# Sheet1.net
KiCad netlist of a schematic drawn in Altium Designer
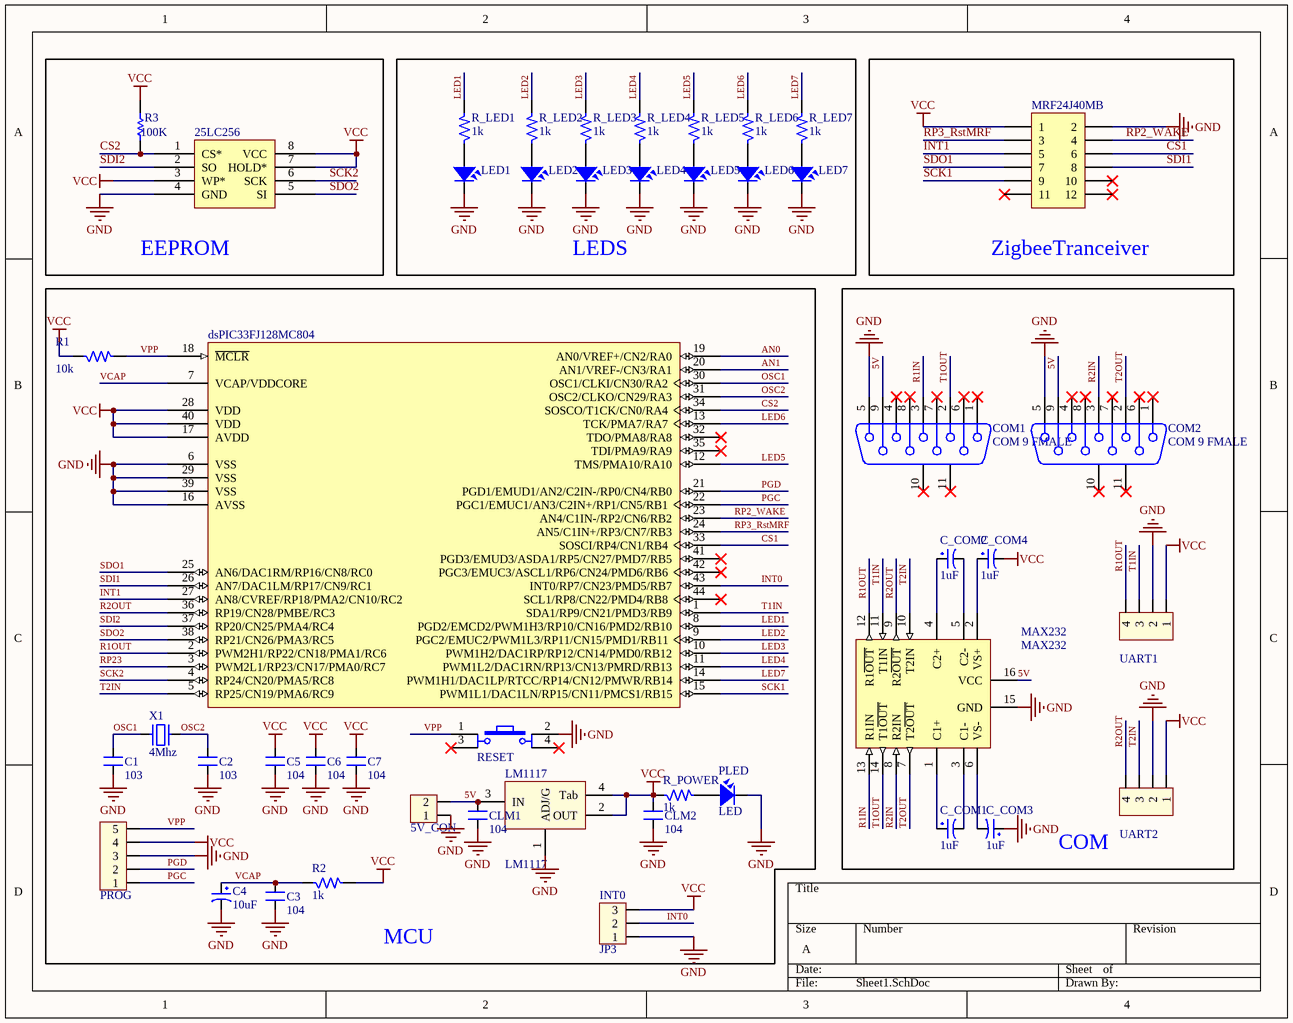
[diagram p0: Sheet1.SchDoc]

(export (version "E")
  (design (tool "Eeschema 10.0.6"))
  (components
    (comp (ref "5V_CON")
      (value "JP2")
      (footprint "CON2")
      (description "Connector 2")
      (libsource (lib "syhaunguyen") (part "Con2"))
    )
    (comp (ref "25LC256") (value "25LC256") (footprint "DIP-8") (libsource (lib "25LC256") (part "25LC256")))
    (comp (ref "C1")
      (value "103")
      (footprint "SM-0805")
      (description "Cap SMD")
      (libsource (lib "syhaunguyen") (part "CM"))
    )
    (comp (ref "C2")
      (value "103")
      (footprint "SM-0805")
      (description "Cap SMD")
      (libsource (lib "syhaunguyen") (part "CM"))
    )
    (comp (ref "C3")
      (value "104")
      (footprint "SM-0805")
      (description "Cap SMD")
      (libsource (lib "syhaunguyen") (part "CM"))
    )
    (comp (ref "C4")
      (value "10uF")
      (footprint "CP1/2")
      (description "Cap P  0,1uF < 22uF , 16 - 50V")
      (libsource (lib "") (part "CP1_1"))
    )
    (comp (ref "C5")
      (value "104")
      (footprint "SM-0805")
      (description "Cap SMD")
      (libsource (lib "syhaunguyen") (part "CM"))
    )
    (comp (ref "C6")
      (value "104")
      (footprint "SM-0805")
      (description "Cap SMD")
      (libsource (lib "syhaunguyen") (part "CM"))
    )
    (comp (ref "C7")
      (value "104")
      (footprint "SM-0805")
      (description "Cap SMD")
      (libsource (lib "syhaunguyen") (part "CM"))
    )
    (comp (ref "CLM1")
      (value "104")
      (footprint "SM-0805")
      (description "Cap np Cremic Value  104pF => 105pF")
      (libsource (lib "syhaunguyen") (part "CN2"))
    )
    (comp (ref "CLM2")
      (value "104")
      (footprint "SM-0805")
      (description "Cap np Cremic Value  104pF => 105pF")
      (libsource (lib "syhaunguyen") (part "CN2"))
    )
    (comp (ref "COM1")
      (value "COM 9 FMALE")
      (footprint "DSB 9-F")
      (description "COM 9")
      (fields (field (name "PUBLISHER") "Altium Limited"))
      (libsource (lib "syhaunguyen") (part "DSB9F"))
    )
    (comp (ref "COM2")
      (value "COM 9 FMALE")
      (footprint "DSB 9-F")
      (description "COM 9")
      (fields (field (name "PUBLISHER") "Altium Limited"))
      (libsource (lib "syhaunguyen") (part "DSB9F"))
    )
    (comp (ref "C_COM1")
      (value "1uF")
      (footprint "CP1/2")
      (description "Cap P  0,1uF < 22uF , 16 - 50V")
      (libsource (lib "syhaunguyen") (part "CP1"))
    )
    (comp (ref "C_COM2")
      (value "1uF")
      (footprint "CP1/2")
      (description "Cap P  0,1uF < 22uF , 16 - 50V")
      (libsource (lib "syhaunguyen") (part "CP1"))
    )
    (comp (ref "C_COM3")
      (value "1uF")
      (footprint "CP1/2")
      (description "Cap P  0,1uF < 22uF , 16 - 50V")
      (libsource (lib "syhaunguyen") (part "CP1"))
    )
    (comp (ref "C_COM4")
      (value "1uF")
      (footprint "CP1/2")
      (description "Cap P  0,1uF < 22uF , 16 - 50V")
      (libsource (lib "syhaunguyen") (part "CP1"))
    )
    (comp (ref "dsPIC33FJ128MC804")
      (value "DSPIC33FJ128MC804T-E/PT")
      (footprint "TQFP-PT44_N")
      (fields (field (name "PUBLISHER") "Altium Limited"))
      (libsource (lib "Microchip DSC 16-Bit dsPIC33F") (part "DSPIC33FJ128MC804T-E/PT"))
    )
    (comp (ref "INT0")
      (value "JP3")
      (footprint "CON3")
      (description "Connector 3")
      (libsource (lib "syhaunguyen") (part "Con3"))
    )
    (comp (ref "LED1")
      (value "LED")
      (footprint "SM-LED-Red")
      (description "Led  Vuong")
      (libsource (lib "syhaunguyen") (part "LED"))
    )
    (comp (ref "LED2")
      (value "LED")
      (footprint "SM-LED-Red")
      (description "Led  Vuong")
      (libsource (lib "syhaunguyen") (part "LED"))
    )
    (comp (ref "LED3")
      (value "LED")
      (footprint "SM-LED-Red")
      (description "Led  Vuong")
      (libsource (lib "syhaunguyen") (part "LED"))
    )
    (comp (ref "LED4")
      (value "LED")
      (footprint "SM-LED-Red")
      (description "Led  Vuong")
      (libsource (lib "syhaunguyen") (part "LED"))
    )
    (comp (ref "LED5")
      (value "LED")
      (footprint "SM-LED-Red")
      (description "Led  Vuong")
      (libsource (lib "syhaunguyen") (part "LED"))
    )
    (comp (ref "LED6")
      (value "LED")
      (footprint "SM-LED-Red")
      (description "Led  Vuong")
      (libsource (lib "syhaunguyen") (part "LED"))
    )
    (comp (ref "LED7")
      (value "LED")
      (footprint "SM-LED-Red")
      (description "Led  Vuong")
      (libsource (lib "syhaunguyen") (part "LED"))
    )
    (comp (ref "LM1117")
      (value "LM1117")
      (footprint "SOT223-4N")
      (description "3v3")
      (libsource (lib "syhaunguyen") (part "LM1117"))
    )
    (comp (ref "MAX232")
      (value "MAX232")
      (footprint "SOP16")
      (description "Dual EIA-232 Driver/Receiver")
      (libsource (lib "syhaunguyen") (part "MAX232"))
    )
    (comp (ref "MRF24J40MB")
      (value "Header 6X2")
      (footprint "MRF24J40MB_board_mini")
      (description "Header, 6-Pin, Dual row")
      (fields (field (name "PUBLISHER") "Altium Limited"))
      (libsource (lib "Miscellaneous Connectors") (part "Header 6X2"))
    )
    (comp (ref "PLED")
      (value "LED")
      (footprint "LED-3")
      (description "Led  Vuong")
      (libsource (lib "syhaunguyen") (part "LED"))
    )
    (comp (ref "PROG")
      (value "JP5")
      (footprint "CON5")
      (description "Connector 5")
      (libsource (lib "syhaunguyen") (part "Con5"))
    )
    (comp (ref "R1")
      (value "10k")
      (footprint "C0805")
      (description "Resistor 1/4W")
      (libsource (lib "syhaunguyen") (part "R"))
    )
    (comp (ref "R2")
      (value "1k")
      (footprint "SM-0805")
      (description "Resistor 1/4W")
      (libsource (lib "syhaunguyen") (part "R"))
    )
    (comp (ref "R3")
      (value "100K")
      (footprint "C0805")
      (description "Semiconductor Resistor")
      (fields (field (name "Comment") "Res Semi") (field (name "PUBLISHER") "Altium Limited"))
      (libsource (lib "Miscellaneous Devices") (part "Res Semi"))
    )
    (comp (ref "RESET")
      (value "SW")
      (footprint "SW4")
      (description "Switch button 4 pin")
      (libsource (lib "syhaunguyen") (part "SW4"))
    )
    (comp (ref "R_LED1")
      (value "1k")
      (footprint "SM-0805")
      (description "Resistor 1/4W")
      (libsource (lib "syhaunguyen") (part "R"))
    )
    (comp (ref "R_LED2")
      (value "1k")
      (footprint "SM-0805")
      (description "Resistor 1/4W")
      (libsource (lib "syhaunguyen") (part "R"))
    )
    (comp (ref "R_LED3")
      (value "1k")
      (footprint "SM-0805")
      (description "Resistor 1/4W")
      (libsource (lib "syhaunguyen") (part "R"))
    )
    (comp (ref "R_LED4")
      (value "1k")
      (footprint "SM-0805")
      (description "Resistor 1/4W")
      (libsource (lib "syhaunguyen") (part "R"))
    )
    (comp (ref "R_LED5")
      (value "1k")
      (footprint "SM-0805")
      (description "Resistor 1/4W")
      (libsource (lib "syhaunguyen") (part "R"))
    )
    (comp (ref "R_LED6")
      (value "1k")
      (footprint "SM-0805")
      (description "Resistor 1/4W")
      (libsource (lib "syhaunguyen") (part "R"))
    )
    (comp (ref "R_LED7")
      (value "1k")
      (footprint "SM-0805")
      (description "Resistor 1/4W")
      (libsource (lib "syhaunguyen") (part "R"))
    )
    (comp (ref "R_POWER")
      (value "1k")
      (footprint "SM-0805")
      (description "Resistor 1/4W")
      (libsource (lib "syhaunguyen") (part "R"))
    )
    (comp (ref "UART1")
      (value "JP4")
      (footprint "CON4")
      (description "Connector 4")
      (libsource (lib "syhaunguyen") (part "Con4"))
    )
    (comp (ref "UART2")
      (value "JP4")
      (footprint "CON4")
      (description "Connector 4")
      (libsource (lib "syhaunguyen") (part "Con4"))
    )
    (comp (ref "X1")
      (value "4Mhz")
      (footprint "XT2")
      (description "Crystal For all Crystal 2pin.")
      (libsource (lib "syhaunguyen") (part "XT2"))
    )
  )
  (nets
    (net (code "1") (name "/5V") (class "Default")
      (node (ref "5V_CON") (pin "2") (pinfunction "2_2") (pintype "passive"))
      (node (ref "CLM1") (pin "2") (pinfunction "2_2") (pintype "passive"))
      (node (ref "COM1") (pin "9") (pinfunction "9_9") (pintype "passive"))
      (node (ref "COM2") (pin "9") (pinfunction "9_9") (pintype "passive"))
      (node (ref "LM1117") (pin "3") (pinfunction "IN_3") (pintype "passive"))
      (node (ref "MAX232") (pin "16") (pinfunction "VCC_16") (pintype "power_in"))
    )
    (net (code "2") (name "/AN0") (class "Default")
      (node (ref "dsPIC33FJ128MC804") (pin "19") (pinfunction "AN0/VREF+/CN2/RA0_19") (pintype "bidirectional"))
    )
    (net (code "3") (name "/AN1") (class "Default")
      (node (ref "dsPIC33FJ128MC804") (pin "20") (pinfunction "AN1/VREF-/CN3/RA1_20") (pintype "bidirectional"))
    )
    (net (code "4") (name "/CS1") (class "Default")
      (node (ref "MRF24J40MB") (pin "6") (pinfunction "6_6") (pintype "passive"))
      (node (ref "dsPIC33FJ128MC804") (pin "33") (pinfunction "SOSCI/RP4/CN1/RB4_33") (pintype "bidirectional"))
    )
    (net (code "5") (name "/CS2") (class "Default")
      (node (ref "25LC256") (pin "1") (pinfunction "CS*_1") (pintype "passive"))
      (node (ref "R3") (pin "1") (pinfunction "1_1") (pintype "passive"))
      (node (ref "dsPIC33FJ128MC804") (pin "34") (pinfunction "SOSCO/T1CK/CN0/RA4_34") (pintype "bidirectional"))
    )
    (net (code "6") (name "/INT0") (class "Default")
      (node (ref "INT0") (pin "2") (pinfunction "2_2") (pintype "passive"))
      (node (ref "dsPIC33FJ128MC804") (pin "43") (pinfunction "INT0/RP7/CN23/PMD5/RB7_43") (pintype "bidirectional"))
    )
    (net (code "7") (name "/INT1") (class "Default")
      (node (ref "MRF24J40MB") (pin "5") (pinfunction "5_5") (pintype "passive"))
      (node (ref "dsPIC33FJ128MC804") (pin "27") (pinfunction "AN8/CVREF/RP18/PMA2/CN10/RC2_27") (pintype "bidirectional"))
    )
    (net (code "8") (name "/LED1") (class "Default")
      (node (ref "R_LED1") (pin "2") (pinfunction "2_2") (pintype "passive"))
      (node (ref "dsPIC33FJ128MC804") (pin "8") (pinfunction "PGD2/EMCD2/PWM1H3/RP10/CN16/PMD2/RB10_8") (pintype "bidirectional"))
    )
    (net (code "9") (name "/LED2") (class "Default")
      (node (ref "R_LED2") (pin "2") (pinfunction "2_2") (pintype "passive"))
      (node (ref "dsPIC33FJ128MC804") (pin "9") (pinfunction "PGC2/EMUC2/PWM1L3/RP11/CN15/PMD1/RB11_9") (pintype "bidirectional"))
    )
    (net (code "10") (name "/LED3") (class "Default")
      (node (ref "R_LED3") (pin "2") (pinfunction "2_2") (pintype "passive"))
      (node (ref "dsPIC33FJ128MC804") (pin "10") (pinfunction "PWM1H2/DAC1RP/RP12/CN14/PMD0/RB12_10") (pintype "bidirectional"))
    )
    (net (code "11") (name "/LED4") (class "Default")
      (node (ref "R_LED4") (pin "2") (pinfunction "2_2") (pintype "passive"))
      (node (ref "dsPIC33FJ128MC804") (pin "11") (pinfunction "PWM1L2/DAC1RN/RP13/CN13/PMRD/RB13_11") (pintype "bidirectional"))
    )
    (net (code "12") (name "/LED5") (class "Default")
      (node (ref "R_LED5") (pin "2") (pinfunction "2_2") (pintype "passive"))
      (node (ref "dsPIC33FJ128MC804") (pin "12") (pinfunction "TMS/PMA10/RA10_12") (pintype "bidirectional"))
    )
    (net (code "13") (name "/LED6") (class "Default")
      (node (ref "R_LED6") (pin "2") (pinfunction "2_2") (pintype "passive"))
      (node (ref "dsPIC33FJ128MC804") (pin "13") (pinfunction "TCK/PMA7/RA7_13") (pintype "bidirectional"))
    )
    (net (code "14") (name "/LED7") (class "Default")
      (node (ref "R_LED7") (pin "2") (pinfunction "2_2") (pintype "passive"))
      (node (ref "dsPIC33FJ128MC804") (pin "14") (pinfunction "PWM1H1/DAC1LP/RTCC/RP14/CN12/PMWR/RB14_14") (pintype "bidirectional"))
    )
    (net (code "15") (name "/OSC1") (class "Default")
      (node (ref "C1") (pin "2") (pinfunction "2_2") (pintype "passive"))
      (node (ref "X1") (pin "1") (pinfunction "1_1") (pintype "passive"))
      (node (ref "dsPIC33FJ128MC804") (pin "30") (pinfunction "OSC1/CLKI/CN30/RA2_30") (pintype "bidirectional"))
    )
    (net (code "16") (name "/OSC2") (class "Default")
      (node (ref "C2") (pin "2") (pinfunction "2_2") (pintype "passive"))
      (node (ref "X1") (pin "2") (pinfunction "2_2") (pintype "passive"))
      (node (ref "dsPIC33FJ128MC804") (pin "31") (pinfunction "OSC2/CLKO/CN29/RA3_31") (pintype "bidirectional"))
    )
    (net (code "17") (name "/PGC") (class "Default")
      (node (ref "PROG") (pin "1") (pinfunction "1_1") (pintype "passive"))
      (node (ref "dsPIC33FJ128MC804") (pin "22") (pinfunction "PGC1/EMUC1/AN3/C2IN+/RP1/CN5/RB1_22") (pintype "bidirectional"))
    )
    (net (code "18") (name "/PGD") (class "Default")
      (node (ref "PROG") (pin "2") (pinfunction "2_2") (pintype "passive"))
      (node (ref "dsPIC33FJ128MC804") (pin "21") (pinfunction "PGD1/EMUD1/AN2/C2IN-/RP0/CN4/RB0_21") (pintype "bidirectional"))
    )
    (net (code "19") (name "/R1IN") (class "Default")
      (node (ref "COM1") (pin "3") (pinfunction "3_3") (pintype "passive"))
      (node (ref "MAX232") (pin "13") (pinfunction "R1IN_13") (pintype "input"))
    )
    (net (code "20") (name "/R1OUT") (class "Default")
      (node (ref "MAX232") (pin "12") (pinfunction "R1~{OUT}_12") (pintype "output"))
      (node (ref "UART1") (pin "4") (pinfunction "4_4") (pintype "passive"))
      (node (ref "dsPIC33FJ128MC804") (pin "2") (pinfunction "PWM2H1/RP22/CN18/PMA1/RC6_2") (pintype "bidirectional"))
    )
    (net (code "21") (name "/R2IN") (class "Default")
      (node (ref "COM2") (pin "3") (pinfunction "3_3") (pintype "passive"))
      (node (ref "MAX232") (pin "8") (pinfunction "R2IN_8") (pintype "input"))
    )
    (net (code "22") (name "/R2OUT") (class "Default")
      (node (ref "MAX232") (pin "9") (pinfunction "R2~{OUT}_9") (pintype "output"))
      (node (ref "UART2") (pin "4") (pinfunction "4_4") (pintype "passive"))
      (node (ref "dsPIC33FJ128MC804") (pin "36") (pinfunction "RP19/CN28/PMBE/RC3_36") (pintype "bidirectional"))
    )
    (net (code "23") (name "/RP2_WAKE") (class "Default")
      (node (ref "MRF24J40MB") (pin "4") (pinfunction "4_4") (pintype "passive"))
      (node (ref "dsPIC33FJ128MC804") (pin "23") (pinfunction "AN4/C1IN-/RP2/CN6/RB2_23") (pintype "bidirectional"))
    )
    (net (code "24") (name "/RP3_RstMRF") (class "Default")
      (node (ref "MRF24J40MB") (pin "3") (pinfunction "3_3") (pintype "passive"))
      (node (ref "dsPIC33FJ128MC804") (pin "24") (pinfunction "AN5/C1IN+/RP3/CN7/RB3_24") (pintype "bidirectional"))
    )
    (net (code "25") (name "/RP23") (class "Default")
      (node (ref "dsPIC33FJ128MC804") (pin "3") (pinfunction "PWM2L1/RP23/CN17/PMA0/RC7_3") (pintype "bidirectional"))
    )
    (net (code "26") (name "/SCK1") (class "Default")
      (node (ref "MRF24J40MB") (pin "9") (pinfunction "9_9") (pintype "passive"))
      (node (ref "dsPIC33FJ128MC804") (pin "15") (pinfunction "PWM1L1/DAC1LN/RP15/CN11/PMCS1/RB15_15") (pintype "bidirectional"))
    )
    (net (code "27") (name "/SCK2") (class "Default")
      (node (ref "25LC256") (pin "6") (pinfunction "SCK_6") (pintype "passive"))
      (node (ref "dsPIC33FJ128MC804") (pin "4") (pinfunction "RP24/CN20/PMA5/RC8_4") (pintype "bidirectional"))
    )
    (net (code "28") (name "/SDI1") (class "Default")
      (node (ref "MRF24J40MB") (pin "8") (pinfunction "8_8") (pintype "passive"))
      (node (ref "dsPIC33FJ128MC804") (pin "26") (pinfunction "AN7/DAC1LM/RP17/CN9/RC1_26") (pintype "bidirectional"))
    )
    (net (code "29") (name "/SDI2") (class "Default")
      (node (ref "25LC256") (pin "2") (pinfunction "SO_2") (pintype "passive"))
      (node (ref "dsPIC33FJ128MC804") (pin "37") (pinfunction "RP20/CN25/PMA4/RC4_37") (pintype "bidirectional"))
    )
    (net (code "30") (name "/SDO1") (class "Default")
      (node (ref "MRF24J40MB") (pin "7") (pinfunction "7_7") (pintype "passive"))
      (node (ref "dsPIC33FJ128MC804") (pin "25") (pinfunction "AN6/DAC1RM/RP16/CN8/RC0_25") (pintype "bidirectional"))
    )
    (net (code "31") (name "/SDO2") (class "Default")
      (node (ref "25LC256") (pin "5") (pinfunction "SI_5") (pintype "passive"))
      (node (ref "dsPIC33FJ128MC804") (pin "38") (pinfunction "RP21/CN26/PMA3/RC5_38") (pintype "bidirectional"))
    )
    (net (code "32") (name "/T1IN") (class "Default")
      (node (ref "MAX232") (pin "11") (pinfunction "T1IN_11") (pintype "input"))
      (node (ref "UART1") (pin "3") (pinfunction "3_3") (pintype "passive"))
      (node (ref "dsPIC33FJ128MC804") (pin "1") (pinfunction "SDA1/RP9/CN21/PMD3/RB9_1") (pintype "bidirectional"))
    )
    (net (code "33") (name "/T1OUT") (class "Default")
      (node (ref "COM1") (pin "2") (pinfunction "2_2") (pintype "passive"))
      (node (ref "MAX232") (pin "14") (pinfunction "T1~{OUT}_14") (pintype "output"))
    )
    (net (code "34") (name "/T2IN") (class "Default")
      (node (ref "MAX232") (pin "10") (pinfunction "T2IN_10") (pintype "input"))
      (node (ref "UART2") (pin "3") (pinfunction "3_3") (pintype "passive"))
      (node (ref "dsPIC33FJ128MC804") (pin "5") (pinfunction "RP25/CN19/PMA6/RC9_5") (pintype "bidirectional"))
    )
    (net (code "35") (name "/T2OUT") (class "Default")
      (node (ref "COM2") (pin "2") (pinfunction "2_2") (pintype "passive"))
      (node (ref "MAX232") (pin "7") (pinfunction "T2~{OUT}_7") (pintype "output"))
    )
    (net (code "36") (name "/VCAP") (class "Default")
      (node (ref "C3") (pin "2") (pinfunction "2_2") (pintype "passive"))
      (node (ref "C4") (pin "1") (pinfunction "1_1") (pintype "passive"))
      (node (ref "R2") (pin "1") (pinfunction "1_1") (pintype "passive"))
      (node (ref "dsPIC33FJ128MC804") (pin "7") (pinfunction "VCAP/VDDCORE_7") (pintype "power_in"))
    )
    (net (code "37") (name "/VPP") (class "Default")
      (node (ref "PROG") (pin "5") (pinfunction "5_5") (pintype "passive"))
      (node (ref "R1") (pin "2") (pinfunction "2_2") (pintype "passive"))
      (node (ref "RESET") (pin "1") (pintype "passive"))
      (node (ref "dsPIC33FJ128MC804") (pin "18") (pinfunction "~{MCLR}_18") (pintype "input"))
    )
    (net (code "38") (name "GND") (class "Default")
      (node (ref "25LC256") (pin "4") (pinfunction "GND_4") (pintype "power_in"))
      (node (ref "5V_CON") (pin "1") (pinfunction "1_1") (pintype "passive"))
      (node (ref "C1") (pin "1") (pinfunction "1_1") (pintype "passive"))
      (node (ref "C2") (pin "1") (pinfunction "1_1") (pintype "passive"))
      (node (ref "C3") (pin "1") (pinfunction "1_1") (pintype "passive"))
      (node (ref "C4") (pin "2") (pinfunction "2_2") (pintype "passive"))
      (node (ref "C5") (pin "1") (pinfunction "1_1") (pintype "passive"))
      (node (ref "C6") (pin "1") (pinfunction "1_1") (pintype "passive"))
      (node (ref "C7") (pin "1") (pinfunction "1_1") (pintype "passive"))
      (node (ref "CLM1") (pin "1") (pinfunction "1_1") (pintype "passive"))
      (node (ref "CLM2") (pin "1") (pinfunction "1_1") (pintype "passive"))
      (node (ref "COM1") (pin "5") (pinfunction "5_5") (pintype "passive"))
      (node (ref "COM2") (pin "5") (pinfunction "5_5") (pintype "passive"))
      (node (ref "C_COM3") (pin "1") (pinfunction "1_1") (pintype "passive"))
      (node (ref "INT0") (pin "1") (pinfunction "1_1") (pintype "passive"))
      (node (ref "LED1") (pin "2") (pinfunction "2_2") (pintype "passive"))
      (node (ref "LED2") (pin "2") (pinfunction "2_2") (pintype "passive"))
      (node (ref "LED3") (pin "2") (pinfunction "2_2") (pintype "passive"))
      (node (ref "LED4") (pin "2") (pinfunction "2_2") (pintype "passive"))
      (node (ref "LED5") (pin "2") (pinfunction "2_2") (pintype "passive"))
      (node (ref "LED6") (pin "2") (pinfunction "2_2") (pintype "passive"))
      (node (ref "LED7") (pin "2") (pinfunction "2_2") (pintype "passive"))
      (node (ref "LM1117") (pin "1") (pinfunction "ADJ/G_1") (pintype "passive"))
      (node (ref "MAX232") (pin "15") (pinfunction "GND_15") (pintype "power_in"))
      (node (ref "MRF24J40MB") (pin "2") (pinfunction "2_2") (pintype "passive"))
      (node (ref "PLED") (pin "2") (pinfunction "2_2") (pintype "passive"))
      (node (ref "PROG") (pin "3") (pinfunction "3_3") (pintype "passive"))
      (node (ref "RESET") (pin "2") (pintype "passive"))
      (node (ref "UART1") (pin "2") (pinfunction "2_2") (pintype "passive"))
      (node (ref "UART2") (pin "2") (pinfunction "2_2") (pintype "passive"))
      (node (ref "dsPIC33FJ128MC804") (pin "16") (pinfunction "AVSS_16") (pintype "power_in"))
      (node (ref "dsPIC33FJ128MC804") (pin "29") (pinfunction "VSS_29") (pintype "power_in"))
      (node (ref "dsPIC33FJ128MC804") (pin "39") (pinfunction "VSS_39") (pintype "power_in"))
      (node (ref "dsPIC33FJ128MC804") (pin "6") (pinfunction "VSS_6") (pintype "power_in"))
    )
    (net (code "39") (name "Net-(LED1-Pad1)") (class "Default")
      (node (ref "LED1") (pin "1") (pinfunction "1_1") (pintype "passive"))
      (node (ref "R_LED1") (pin "1") (pinfunction "1_1") (pintype "passive"))
    )
    (net (code "40") (name "Net-(LED2-Pad1)") (class "Default")
      (node (ref "LED2") (pin "1") (pinfunction "1_1") (pintype "passive"))
      (node (ref "R_LED2") (pin "1") (pinfunction "1_1") (pintype "passive"))
    )
    (net (code "41") (name "Net-(LED3-Pad1)") (class "Default")
      (node (ref "LED3") (pin "1") (pinfunction "1_1") (pintype "passive"))
      (node (ref "R_LED3") (pin "1") (pinfunction "1_1") (pintype "passive"))
    )
    (net (code "42") (name "Net-(LED4-Pad1)") (class "Default")
      (node (ref "LED4") (pin "1") (pinfunction "1_1") (pintype "passive"))
      (node (ref "R_LED4") (pin "1") (pinfunction "1_1") (pintype "passive"))
    )
    (net (code "43") (name "Net-(LED5-Pad1)") (class "Default")
      (node (ref "LED5") (pin "1") (pinfunction "1_1") (pintype "passive"))
      (node (ref "R_LED5") (pin "1") (pinfunction "1_1") (pintype "passive"))
    )
    (net (code "44") (name "Net-(LED6-Pad1)") (class "Default")
      (node (ref "LED6") (pin "1") (pinfunction "1_1") (pintype "passive"))
      (node (ref "R_LED6") (pin "1") (pinfunction "1_1") (pintype "passive"))
    )
    (net (code "45") (name "Net-(LED7-Pad1)") (class "Default")
      (node (ref "LED7") (pin "1") (pinfunction "1_1") (pintype "passive"))
      (node (ref "R_LED7") (pin "1") (pinfunction "1_1") (pintype "passive"))
    )
    (net (code "46") (name "Net-(MAX232-C1+)") (class "Default")
      (node (ref "C_COM1") (pin "1") (pinfunction "1_1") (pintype "passive"))
      (node (ref "MAX232") (pin "1") (pinfunction "C1+_1") (pintype "passive"))
    )
    (net (code "47") (name "Net-(MAX232-C1-)") (class "Default")
      (node (ref "C_COM1") (pin "2") (pinfunction "2_2") (pintype "passive"))
      (node (ref "MAX232") (pin "3") (pinfunction "C1-_3") (pintype "passive"))
    )
    (net (code "48") (name "Net-(MAX232-C2+)") (class "Default")
      (node (ref "C_COM2") (pin "1") (pinfunction "1_1") (pintype "passive"))
      (node (ref "MAX232") (pin "4") (pinfunction "C2+_4") (pintype "passive"))
    )
    (net (code "49") (name "Net-(MAX232-C2-)") (class "Default")
      (node (ref "C_COM2") (pin "2") (pinfunction "2_2") (pintype "passive"))
      (node (ref "MAX232") (pin "5") (pinfunction "C2-_5") (pintype "passive"))
    )
    (net (code "50") (name "Net-(MAX232-VS+)") (class "Default")
      (node (ref "C_COM4") (pin "1") (pinfunction "1_1") (pintype "passive"))
      (node (ref "MAX232") (pin "2") (pinfunction "VS+_2") (pintype "power_in"))
    )
    (net (code "51") (name "Net-(MAX232-VS-)") (class "Default")
      (node (ref "C_COM3") (pin "2") (pinfunction "2_2") (pintype "passive"))
      (node (ref "MAX232") (pin "6") (pinfunction "VS-_6") (pintype "power_in"))
    )
    (net (code "52") (name "Net-(PLED-Pad1)") (class "Default")
      (node (ref "PLED") (pin "1") (pinfunction "1_1") (pintype "passive"))
      (node (ref "R_POWER") (pin "2") (pinfunction "2_2") (pintype "passive"))
    )
    (net (code "53") (name "VCC") (class "Default")
      (node (ref "25LC256") (pin "3") (pinfunction "WP*_3") (pintype "passive"))
      (node (ref "25LC256") (pin "7") (pinfunction "HOLD*_7") (pintype "passive"))
      (node (ref "25LC256") (pin "8") (pinfunction "VCC_8") (pintype "power_in"))
      (node (ref "C5") (pin "2") (pinfunction "2_2") (pintype "passive"))
      (node (ref "C6") (pin "2") (pinfunction "2_2") (pintype "passive"))
      (node (ref "C7") (pin "2") (pinfunction "2_2") (pintype "passive"))
      (node (ref "CLM2") (pin "2") (pinfunction "2_2") (pintype "passive"))
      (node (ref "C_COM4") (pin "2") (pinfunction "2_2") (pintype "passive"))
      (node (ref "INT0") (pin "3") (pinfunction "3_3") (pintype "passive"))
      (node (ref "LM1117") (pin "2") (pinfunction "OUT_2") (pintype "passive"))
      (node (ref "LM1117") (pin "4") (pinfunction "Tab_4") (pintype "passive"))
      (node (ref "MRF24J40MB") (pin "1") (pinfunction "1_1") (pintype "passive"))
      (node (ref "PROG") (pin "4") (pinfunction "4_4") (pintype "passive"))
      (node (ref "R1") (pin "1") (pinfunction "1_1") (pintype "passive"))
      (node (ref "R2") (pin "2") (pinfunction "2_2") (pintype "passive"))
      (node (ref "R3") (pin "2") (pinfunction "2_2") (pintype "passive"))
      (node (ref "R_POWER") (pin "1") (pinfunction "1_1") (pintype "passive"))
      (node (ref "UART1") (pin "1") (pinfunction "1_1") (pintype "passive"))
      (node (ref "UART2") (pin "1") (pinfunction "1_1") (pintype "passive"))
      (node (ref "dsPIC33FJ128MC804") (pin "17") (pinfunction "AVDD_17") (pintype "power_in"))
      (node (ref "dsPIC33FJ128MC804") (pin "28") (pinfunction "VDD_28") (pintype "power_in"))
      (node (ref "dsPIC33FJ128MC804") (pin "40") (pinfunction "VDD_40") (pintype "power_in"))
    )
    (net (code "54") (name "unconnected-(COM1-MH1-Pad10)") (class "Default")
      (node (ref "COM1") (pin "10") (pinfunction "MH1_10") (pintype "passive+no_connect"))
    )
    (net (code "55") (name "unconnected-(COM1-MH2-Pad11)") (class "Default")
      (node (ref "COM1") (pin "11") (pinfunction "MH2_11") (pintype "passive+no_connect"))
    )
    (net (code "56") (name "unconnected-(COM1-Pad1)") (class "Default")
      (node (ref "COM1") (pin "1") (pinfunction "1_1") (pintype "passive+no_connect"))
    )
    (net (code "57") (name "unconnected-(COM1-Pad4)") (class "Default")
      (node (ref "COM1") (pin "4") (pinfunction "4_4") (pintype "passive+no_connect"))
    )
    (net (code "58") (name "unconnected-(COM1-Pad6)") (class "Default")
      (node (ref "COM1") (pin "6") (pinfunction "6_6") (pintype "passive+no_connect"))
    )
    (net (code "59") (name "unconnected-(COM1-Pad7)") (class "Default")
      (node (ref "COM1") (pin "7") (pinfunction "7_7") (pintype "passive+no_connect"))
    )
    (net (code "60") (name "unconnected-(COM1-Pad8)") (class "Default")
      (node (ref "COM1") (pin "8") (pinfunction "8_8") (pintype "passive+no_connect"))
    )
    (net (code "61") (name "unconnected-(COM2-MH1-Pad10)") (class "Default")
      (node (ref "COM2") (pin "10") (pinfunction "MH1_10") (pintype "passive+no_connect"))
    )
    (net (code "62") (name "unconnected-(COM2-MH2-Pad11)") (class "Default")
      (node (ref "COM2") (pin "11") (pinfunction "MH2_11") (pintype "passive+no_connect"))
    )
    (net (code "63") (name "unconnected-(COM2-Pad1)") (class "Default")
      (node (ref "COM2") (pin "1") (pinfunction "1_1") (pintype "passive+no_connect"))
    )
    (net (code "64") (name "unconnected-(COM2-Pad4)") (class "Default")
      (node (ref "COM2") (pin "4") (pinfunction "4_4") (pintype "passive+no_connect"))
    )
    (net (code "65") (name "unconnected-(COM2-Pad6)") (class "Default")
      (node (ref "COM2") (pin "6") (pinfunction "6_6") (pintype "passive+no_connect"))
    )
    (net (code "66") (name "unconnected-(COM2-Pad7)") (class "Default")
      (node (ref "COM2") (pin "7") (pinfunction "7_7") (pintype "passive+no_connect"))
    )
    (net (code "67") (name "unconnected-(COM2-Pad8)") (class "Default")
      (node (ref "COM2") (pin "8") (pinfunction "8_8") (pintype "passive+no_connect"))
    )
    (net (code "68") (name "unconnected-(MRF24J40MB-Pad10)") (class "Default")
      (node (ref "MRF24J40MB") (pin "10") (pinfunction "10_10") (pintype "passive+no_connect"))
    )
    (net (code "69") (name "unconnected-(MRF24J40MB-Pad11)") (class "Default")
      (node (ref "MRF24J40MB") (pin "11") (pinfunction "11_11") (pintype "passive+no_connect"))
    )
    (net (code "70") (name "unconnected-(MRF24J40MB-Pad12)") (class "Default")
      (node (ref "MRF24J40MB") (pin "12") (pinfunction "12_12") (pintype "passive+no_connect"))
    )
    (net (code "71") (name "unconnected-(RESET-Pad3)") (class "Default")
      (node (ref "RESET") (pin "3") (pintype "passive+no_connect"))
    )
    (net (code "72") (name "unconnected-(RESET-Pad4)") (class "Default")
      (node (ref "RESET") (pin "4") (pintype "passive+no_connect"))
    )
    (net (code "73") (name "unconnected-(dsPIC33FJ128MC804-PGC3{slash}EMUC3{slash}ASCL1{slash}RP6{slash}CN24{slash}PMD6{slash}RB6-Pad42)") (class "Default")
      (node (ref "dsPIC33FJ128MC804") (pin "42") (pinfunction "PGC3/EMUC3/ASCL1/RP6/CN24/PMD6/RB6_42") (pintype "bidirectional+no_connect"))
    )
    (net (code "74") (name "unconnected-(dsPIC33FJ128MC804-PGD3{slash}EMUD3{slash}ASDA1{slash}RP5{slash}CN27{slash}PMD7{slash}RB5-Pad41)") (class "Default")
      (node (ref "dsPIC33FJ128MC804") (pin "41") (pinfunction "PGD3/EMUD3/ASDA1/RP5/CN27/PMD7/RB5_41") (pintype "bidirectional+no_connect"))
    )
    (net (code "75") (name "unconnected-(dsPIC33FJ128MC804-SCL1{slash}RP8{slash}CN22{slash}PMD4{slash}RB8-Pad44)") (class "Default")
      (node (ref "dsPIC33FJ128MC804") (pin "44") (pinfunction "SCL1/RP8/CN22/PMD4/RB8_44") (pintype "bidirectional+no_connect"))
    )
    (net (code "76") (name "unconnected-(dsPIC33FJ128MC804-TDI{slash}PMA9{slash}RA9-Pad35)") (class "Default")
      (node (ref "dsPIC33FJ128MC804") (pin "35") (pinfunction "TDI/PMA9/RA9_35") (pintype "bidirectional+no_connect"))
    )
    (net (code "77") (name "unconnected-(dsPIC33FJ128MC804-TDO{slash}PMA8{slash}RA8-Pad32)") (class "Default")
      (node (ref "dsPIC33FJ128MC804") (pin "32") (pinfunction "TDO/PMA8/RA8_32") (pintype "bidirectional+no_connect"))
    )
  )
)
